# PPS_IN.net
KiCad netlist of a schematic drawn in Altium Designer
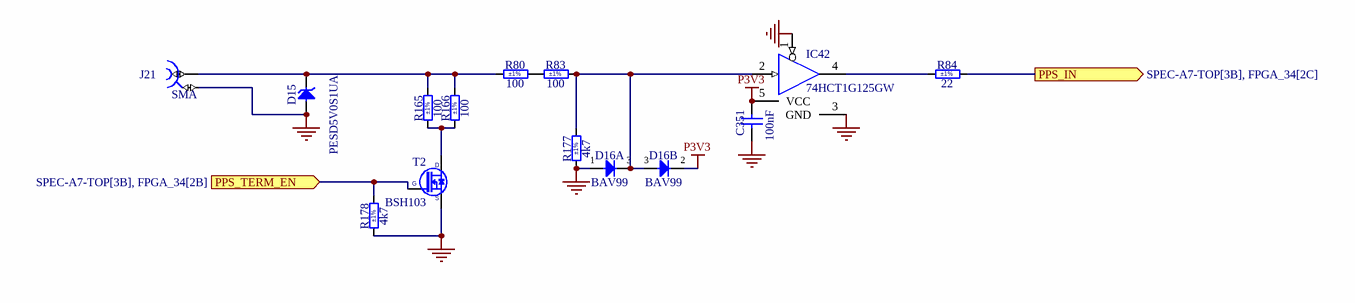
[diagram p0: PPS_IN.SchDoc]

(export (version "E")
  (design (tool "Eeschema 10.0.6"))
  (components
    (comp (ref "C351")
      (value "100nF")
      (footprint "CAPC0603X33N")
      (description "Non-polarised capacitor")
      (fields
        (field (name "PART NUMBER") "CC0201_100NF_6.3V_10%_X5R")
        (field (name "VOLTAGE") "6.3V")
        (field (name "AUTHOR") "CERN DEM JLC")
      )
      (libsource (lib "Capacitors") (part "Capacitor - non polarized"))
    )
    (comp (ref "D15")
      (value "PESD5V0S1UA")
      (footprint "SOD2512X110N")
      (description "Transient Voltage Suppressor Diode (Uni-Directional)")
      (fields
        (field (name "VOLTAGE") "5V")
        (field (name "POWER") "890W")
        (field (name "AUTHOR") "CERN DEM JLC")
      )
      (libsource (lib "ICs And Semiconductors") (part "Diode TVS Uni-Directional"))
    )
    (comp (ref "D16")
      (value "BAV99")
      (footprint "SOT95P240X110-3N")
      (description "Serial Diode")
      (fields
        (field (name "VOLTAGE") "70V")
        (field (name "POWER") "350mW")
        (field (name "AUTHOR") "CERN DEM JLC")
      )
      (libsource (lib "ICs And Semiconductors") (part "Diode x2 A1C3_A3C2"))
    )
    (comp (ref "IC42")
      (value "74HCT1G125GW")
      (footprint "SOT65P210X110-5N")
      (description "Single Bus Buffer Gate With 3-State Output")
      (fields (field (name "MANUFACTURER") "NEXPERIA") (field (name "AUTHOR") "CERN DEM JMW"))
      (libsource (lib "ICs And Semiconductors") (part "741G125"))
    )
    (comp (ref "J21")
      (value "SMA")
      (footprint "DELOCK_65848")
      (description "50 Ohm Through Hole SMA Right Angle PCB Jack")
      (fields
        (field (name "PART NUMBER") "DELOCK_65848")
        (field (name "MANUFACTURER") "DELOCK")
        (field (name "AUTHOR") "GK")
      )
      (libsource (lib "Connectors") (part "CON_SMA_DELOCK_65848"))
    )
    (comp (ref "R80")
      (value "100")
      (footprint "RESC1005X40N")
      (description "Resistor - 1%")
      (fields
        (field (name "TOLERANCE") "±1%")
        (field (name "PART NUMBER") "R0402_100R_1%_0.0625W_100PPM")
        (field (name "POWER") "0.0625W")
        (field (name "AUTHOR") "CERN DEM JLC")
      )
      (libsource (lib "Resistors") (part "Resistor - 1%"))
    )
    (comp (ref "R83")
      (value "100")
      (footprint "RESC1005X40N")
      (description "Resistor - 1%")
      (fields
        (field (name "TOLERANCE") "±1%")
        (field (name "PART NUMBER") "R0402_100R_1%_0.0625W_100PPM")
        (field (name "POWER") "0.0625W")
        (field (name "AUTHOR") "CERN DEM JLC")
      )
      (libsource (lib "Resistors") (part "Resistor - 1%"))
    )
    (comp (ref "R84")
      (value "22")
      (footprint "RESC1005X40N")
      (description "Resistor - 1%")
      (fields
        (field (name "TOLERANCE") "±1%")
        (field (name "PART NUMBER") "R0402_22R_1%_0.0625W_100PPM")
        (field (name "POWER") "0.0625W")
        (field (name "AUTHOR") "CERN DEM JLC")
      )
      (libsource (lib "Resistors") (part "Resistor - 1%"))
    )
    (comp (ref "R165")
      (value "100")
      (footprint "RESC1005X40N")
      (description "Resistor - 1%")
      (fields
        (field (name "TOLERANCE") "±1%")
        (field (name "PART NUMBER") "R0402_100R_1%_0.0625W_100PPM")
        (field (name "POWER") "0.0625W")
        (field (name "AUTHOR") "CERN DEM JLC")
      )
      (libsource (lib "Resistors") (part "Resistor - 1%"))
    )
    (comp (ref "R166")
      (value "100")
      (footprint "RESC1005X40N")
      (description "Resistor - 1%")
      (fields
        (field (name "TOLERANCE") "±1%")
        (field (name "PART NUMBER") "R0402_100R_1%_0.0625W_100PPM")
        (field (name "POWER") "0.0625W")
        (field (name "AUTHOR") "CERN DEM JLC")
      )
      (libsource (lib "Resistors") (part "Resistor - 1%"))
    )
    (comp (ref "R177")
      (value "4k7")
      (footprint "RESC1005X40N")
      (description "Resistor - 1%")
      (fields
        (field (name "TOLERANCE") "±1%")
        (field (name "PART NUMBER") "R0402_4K7_1%_0.0625W_100PPM")
        (field (name "POWER") "0.0625W")
        (field (name "AUTHOR") "CERN DEM JLC")
      )
      (libsource (lib "Resistors") (part "Resistor - 1%"))
    )
    (comp (ref "R178")
      (value "4k7")
      (footprint "RESC1005X40N")
      (description "Resistor - 1%")
      (fields
        (field (name "TOLERANCE") "±1%")
        (field (name "PART NUMBER") "R0402_4K7_1%_0.0625W_100PPM")
        (field (name "POWER") "0.0625W")
        (field (name "AUTHOR") "CERN DEM JLC")
      )
      (libsource (lib "Resistors") (part "Resistor - 1%"))
    )
    (comp (ref "T2")
      (value "BSH103")
      (footprint "SOT95P230X110-3N")
      (description "N-CHANNEL MOSFET WITH DIODE")
      (fields (field (name "MANUFACTURER") "NEXPERIA") (field (name "AUTHOR") "CERN DEM JLC"))
      (libsource (lib "ICs And Semiconductors") (part "N-MOSFET-D 1G 2S 3D"))
    )
  )
  (nets
    (net (code "1") (name "/PPS_IN") (class "Default")
      (node (ref "R84") (pin "2") (pinfunction "2_2") (pintype "passive"))
    )
    (net (code "2") (name "/PPS_TERM_EN") (class "Default")
      (node (ref "R178") (pin "2") (pinfunction "2_2") (pintype "passive"))
      (node (ref "T2") (pin "1") (pinfunction "G_1") (pintype "passive"))
    )
    (net (code "3") (name "GND") (class "Default")
      (node (ref "C351") (pin "1") (pinfunction "1_1") (pintype "passive"))
      (node (ref "D15") (pin "2") (pinfunction "A_2") (pintype "passive"))
      (node (ref "D16") (pin "1") (pinfunction "A_1") (pintype "passive"))
      (node (ref "IC42") (pin "1") (pinfunction "~{G}_1") (pintype "input"))
      (node (ref "IC42") (pin "3") (pinfunction "GND_3") (pintype "power_in"))
      (node (ref "J21") (pin "2") (pinfunction "2_2") (pintype "bidirectional"))
      (node (ref "R177") (pin "1") (pinfunction "1_1") (pintype "passive"))
      (node (ref "R178") (pin "1") (pinfunction "1_1") (pintype "passive"))
      (node (ref "T2") (pin "2") (pinfunction "S_2") (pintype "passive"))
    )
    (net (code "4") (name "Net-(D15-C)") (class "Default")
      (node (ref "D15") (pin "1") (pinfunction "C_1") (pintype "passive"))
      (node (ref "J21") (pin "1") (pinfunction "1_1") (pintype "bidirectional"))
      (node (ref "R165") (pin "2") (pinfunction "2_2") (pintype "passive"))
      (node (ref "R166") (pin "2") (pinfunction "2_2") (pintype "passive"))
      (node (ref "R80") (pin "1") (pinfunction "1_1") (pintype "passive"))
    )
    (net (code "5") (name "Net-(D16A-COMAC)") (class "Default")
      (node (ref "D16") (pin "3") (pinfunction "COMAC_3") (pintype "passive"))
      (node (ref "IC42") (pin "2") (pinfunction "IN_2") (pintype "input"))
      (node (ref "R177") (pin "2") (pinfunction "2_2") (pintype "passive"))
      (node (ref "R83") (pin "2") (pinfunction "2_2") (pintype "passive"))
    )
    (net (code "6") (name "Net-(IC42-OUT)") (class "Default")
      (node (ref "IC42") (pin "4") (pinfunction "OUT_4") (pintype "tri_state"))
      (node (ref "R84") (pin "1") (pinfunction "1_1") (pintype "passive"))
    )
    (net (code "7") (name "Net-(R80-Pad2)") (class "Default")
      (node (ref "R80") (pin "2") (pinfunction "2_2") (pintype "passive"))
      (node (ref "R83") (pin "1") (pinfunction "1_1") (pintype "passive"))
    )
    (net (code "8") (name "Net-(T2-D)") (class "Default")
      (node (ref "R165") (pin "1") (pinfunction "1_1") (pintype "passive"))
      (node (ref "R166") (pin "1") (pinfunction "1_1") (pintype "passive"))
      (node (ref "T2") (pin "3") (pinfunction "D_3") (pintype "passive"))
    )
    (net (code "9") (name "P3V3") (class "Default")
      (node (ref "C351") (pin "2") (pinfunction "2_2") (pintype "passive"))
      (node (ref "D16") (pin "2") (pinfunction "C_2") (pintype "passive"))
      (node (ref "IC42") (pin "5") (pinfunction "VCC_5") (pintype "power_in"))
    )
  )
)
